# sch.net
KiCad netlist of a schematic drawn in Altium Designer
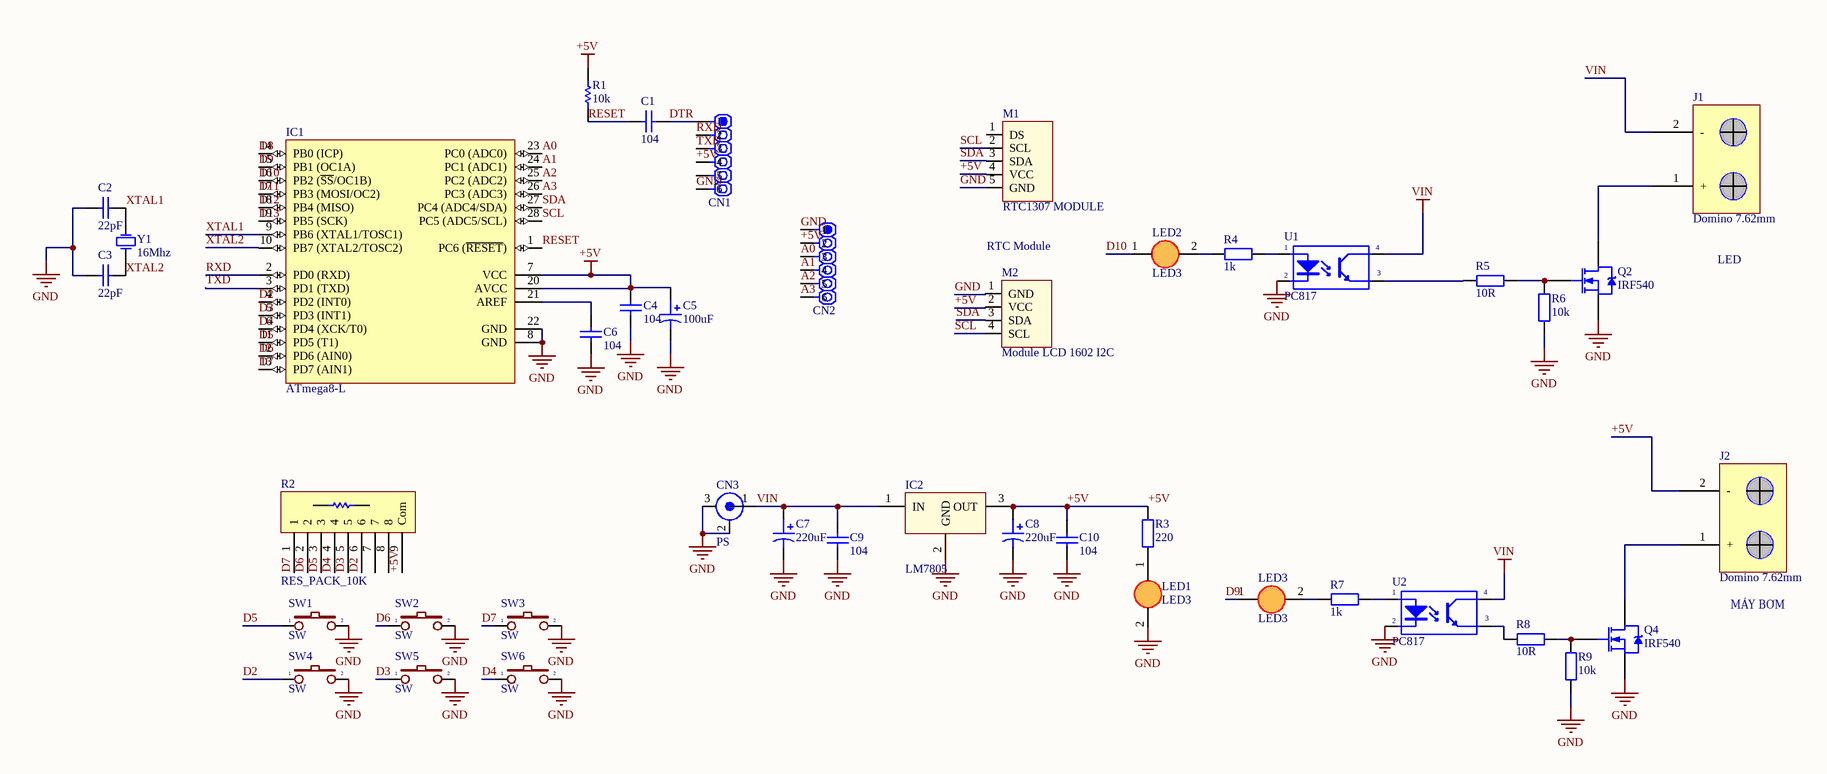
[diagram p0: sch.SchDoc]

(export (version "E")
  (design (tool "Eeschema 10.0.6"))
  (components
    (comp (ref "C1")
      (value "104")
      (footprint "C-NP-0805")
      (description "Non-polarized Capacitor")
      (fields (field (name "Comment") "Cap Non-pol") (field (name "PUBLISHER") "Altium Limited"))
      (libsource (lib "anhlibsch") (part "Cap Non-pol"))
    )
    (comp (ref "C2")
      (value "22pF")
      (footprint "C-NP-0805")
      (description "Non-polarized Capacitor")
      (fields (field (name "Comment") "Cap Non-pol") (field (name "PUBLISHER") "Altium Limited"))
      (libsource (lib "anhlibsch") (part "Cap Non-pol"))
    )
    (comp (ref "C3")
      (value "22pF")
      (footprint "C-NP-0805")
      (description "Non-polarized Capacitor")
      (fields (field (name "Comment") "Cap Non-pol") (field (name "PUBLISHER") "Altium Limited"))
      (libsource (lib "anhlibsch") (part "Cap Non-pol"))
    )
    (comp (ref "C4")
      (value "104")
      (footprint "C-NP-0805")
      (description "Non-polarized Capacitor")
      (fields (field (name "Comment") "Cap Non-pol") (field (name "PUBLISHER") "Altium Limited"))
      (libsource (lib "anhlibsch") (part "Cap Non-pol"))
    )
    (comp (ref "C5")
      (value "100uF")
      (footprint "RADIAL D")
      (description "Polarized Capacitor")
      (fields (field (name "Comment") "Cap Pol") (field (name "PUBLISHER") "Altium Limited"))
      (libsource (lib "anhlibsch") (part "Cap Pol"))
    )
    (comp (ref "C6")
      (value "104")
      (footprint "C-NP-0805")
      (description "Non-polarized Capacitor")
      (fields (field (name "Comment") "Cap Non-pol") (field (name "PUBLISHER") "Altium Limited"))
      (libsource (lib "anhlibsch") (part "Cap Non-pol"))
    )
    (comp (ref "C7")
      (value "220uF")
      (footprint "RADIAL E")
      (description "Polarized Capacitor")
      (fields (field (name "Comment") "Cap Pol") (field (name "PUBLISHER") "Altium Limited"))
      (libsource (lib "anhlibsch") (part "Cap Pol"))
    )
    (comp (ref "C8")
      (value "220uF")
      (footprint "RADIAL E")
      (description "Polarized Capacitor")
      (fields (field (name "Comment") "Cap Pol") (field (name "PUBLISHER") "Altium Limited"))
      (libsource (lib "anhlibsch") (part "Cap Pol"))
    )
    (comp (ref "C9")
      (value "104")
      (footprint "Cap Non-Pol 3mm")
      (description "Non-polarized Capacitor")
      (fields (field (name "Comment") "Cap Non-pol") (field (name "PUBLISHER") "Altium Limited"))
      (libsource (lib "anhlibsch") (part "Cap Non-pol"))
    )
    (comp (ref "C10")
      (value "104")
      (footprint "Cap Non-Pol 3mm")
      (description "Non-polarized Capacitor")
      (fields (field (name "Comment") "Cap Non-pol") (field (name "PUBLISHER") "Altium Limited"))
      (libsource (lib "anhlibsch") (part "Cap Non-pol"))
    )
    (comp (ref "CN1")
      (value "IO")
      (footprint "CON.HDR1X6")
      (description "Header 1x6")
      (fields (field (name "PUBLISHER") "Hoang Nguyen"))
      (libsource (lib "anhlibsch") (part "CON.HDR1x6"))
    )
    (comp (ref "CN2")
      (value "IO")
      (footprint "CON.HDR1X6")
      (description "Header 1x6")
      (fields (field (name "PUBLISHER") "Hoang Nguyen"))
      (libsource (lib "anhlibsch") (part "CON.HDR1x6"))
    )
    (comp (ref "CN3")
      (value "PS")
      (footprint "JACK DC")
      (description "DC Power Jack, 2.5mm, KLD Series, PCB Mount")
      (libsource (lib "anhlibsch") (part "CON.DCjack"))
    )
    (comp (ref "IC1")
      (value "ATmega8-L")
      (footprint "DIP28/W0.3")
      (description "8-Bit AVR Microcontroller with 8K Bytes of In-System Programmable Flash Memory")
      (libsource (lib "anhlibsch") (part "ATmega8-L"))
    )
    (comp (ref "IC2")
      (value "LM7805")
      (footprint "QTO-220")
      (description "On ap +, from + 5 to + 24VDC")
      (libsource (lib "anhlibsch") (part "LM78xx_1"))
    )
    (comp (ref "J1")
      (value "Domino 7.62mm")
      (footprint "KF7.62")
      (libsource (lib "anhlibsch") (part "Con2-7.62mm"))
    )
    (comp (ref "J2")
      (value "Domino 7.62mm")
      (footprint "KF7.62")
      (libsource (lib "anhlibsch") (part "Con2-7.62mm"))
    )
    (comp (ref "LED1")
      (value "LED3")
      (footprint "LED3mm")
      (description "LED 3mm")
      (libsource (lib "anhlibsch") (part "LED 3mm"))
    )
    (comp (ref "LED2")
      (value "LED3")
      (footprint "LED3mm")
      (description "LED 3mm")
      (libsource (lib "anhlibsch") (part "LED 3mm"))
    )
    (comp (ref "LED3")
      (value "LED3")
      (footprint "LED3mm")
      (description "LED 3mm")
      (libsource (lib "anhlibsch") (part "LED 3mm"))
    )
    (comp (ref "M1")
      (value "RTC1307 MODULE")
      (footprint "RTCmODULE")
      (libsource (lib "anhlibsch") (part "RTC1307_MODULE"))
    )
    (comp (ref "M2")
      (value "Module LCD 1602 I2C")
      (footprint "LCD1602_I2C")
      (libsource (lib "anhlibsch") (part "LCD1602_I2C"))
    )
    (comp (ref "Q2")
      (value "IRF540")
      (footprint "TO-220-3")
      (description "HEXFET N-Channel Power MOSFET")
      (fields (field (name "PUBLISHER") "Altium Limited"))
      (libsource (lib "anhlibsch") (part "IRF540"))
    )
    (comp (ref "Q4")
      (value "IRF540")
      (footprint "TO-220-3")
      (description "HEXFET N-Channel Power MOSFET")
      (fields (field (name "PUBLISHER") "Altium Limited"))
      (libsource (lib "anhlibsch") (part "IRF540"))
    )
    (comp (ref "R1")
      (value "10k")
      (footprint "R-0805")
      (description "Resistor")
      (fields (field (name "Comment") "RESISTOR") (field (name "PUBLISHER") "Altium Limited"))
      (libsource (lib "anhlibsch") (part "RESISTOR"))
    )
    (comp (ref "R2")
      (value "RES_PACK_10K")
      (footprint "Res Array")
      (description "Isolated Resistor Network")
      (fields (field (name "PUBLISHER") "Altium Limited"))
      (libsource (lib "anhlibsch") (part "RES_PACK_8R"))
    )
    (comp (ref "R3")
      (value "220")
      (footprint "R1/4W")
      (description "Resistor 1/4W")
      (libsource (lib "anhlibsch") (part "R1/4W"))
    )
    (comp (ref "R4")
      (value "1k")
      (footprint "R1/4W")
      (description "Resistor 1/4W")
      (libsource (lib "anhlibsch") (part "R1/4W"))
    )
    (comp (ref "R5")
      (value "10R")
      (footprint "R1/4W")
      (description "Resistor 1/4W")
      (libsource (lib "anhlibsch") (part "R1/4W"))
    )
    (comp (ref "R6")
      (value "10k")
      (footprint "R1/4W")
      (description "Resistor 1/4W")
      (libsource (lib "anhlibsch") (part "R1/4W"))
    )
    (comp (ref "R7")
      (value "1k")
      (footprint "R1/4W")
      (description "Resistor 1/4W")
      (libsource (lib "anhlibsch") (part "R1/4W"))
    )
    (comp (ref "R8")
      (value "10R")
      (footprint "R1/4W")
      (description "Resistor 1/4W")
      (libsource (lib "anhlibsch") (part "R1/4W"))
    )
    (comp (ref "R9")
      (value "10k")
      (footprint "R1/4W")
      (description "Resistor 1/4W")
      (libsource (lib "anhlibsch") (part "R1/4W"))
    )
    (comp (ref "SW1")
      (value "SW")
      (footprint "SW2")
      (description "Switch button 2 pin")
      (libsource (lib "anhlibsch") (part "SW2"))
    )
    (comp (ref "SW2")
      (value "SW")
      (footprint "SW2")
      (description "Switch button 2 pin")
      (libsource (lib "anhlibsch") (part "SW2"))
    )
    (comp (ref "SW3")
      (value "SW")
      (footprint "SW2")
      (description "Switch button 2 pin")
      (libsource (lib "anhlibsch") (part "SW2"))
    )
    (comp (ref "SW4")
      (value "SW")
      (footprint "SW2")
      (description "Switch button 2 pin")
      (libsource (lib "anhlibsch") (part "SW2"))
    )
    (comp (ref "SW5")
      (value "SW")
      (footprint "SW2")
      (description "Switch button 2 pin")
      (libsource (lib "anhlibsch") (part "SW2"))
    )
    (comp (ref "SW6")
      (value "SW")
      (footprint "SW2")
      (description "Switch button 2 pin")
      (libsource (lib "anhlibsch") (part "SW2"))
    )
    (comp (ref "U1")
      (value "PC817")
      (footprint "DIP4/W0.3")
      (description "Single Opto")
      (libsource (lib "anhlibsch") (part "PC817_1"))
    )
    (comp (ref "U2")
      (value "PC817")
      (footprint "DIP4/W0.3")
      (description "Single Opto")
      (libsource (lib "anhlibsch") (part "PC817_1"))
    )
    (comp (ref "Y1")
      (value "16Mhz")
      (footprint "XTAL")
      (description "Crystal Oscillator")
      (fields (field (name "PUBLISHER") "Altium Limited"))
      (libsource (lib "anhlibsch") (part "XTAL"))
    )
  )
  (nets
    (net (code "1") (name "+5V") (class "Default")
      (node (ref "C10") (pin "1") (pinfunction "1_1") (pintype "passive"))
      (node (ref "C4") (pin "2") (pinfunction "2_2") (pintype "passive"))
      (node (ref "C5") (pin "1") (pinfunction "1_1") (pintype "passive"))
      (node (ref "C8") (pin "1") (pinfunction "1_1") (pintype "passive"))
      (node (ref "CN1") (pin "4") (pinfunction "4_4") (pintype "passive"))
      (node (ref "CN2") (pin "2") (pinfunction "2_2") (pintype "passive"))
      (node (ref "IC1") (pin "20") (pinfunction "AVCC_20") (pintype "power_in"))
      (node (ref "IC1") (pin "7") (pinfunction "VCC_7") (pintype "power_in"))
      (node (ref "IC2") (pin "3") (pinfunction "OUT_3") (pintype "passive"))
      (node (ref "J2") (pin "2") (pinfunction "-_2") (pintype "passive"))
      (node (ref "M1") (pin "4") (pinfunction "VCC_4") (pintype "passive"))
      (node (ref "M2") (pin "2") (pinfunction "VCC_2") (pintype "passive"))
      (node (ref "R1") (pin "2") (pinfunction "2_2") (pintype "passive"))
      (node (ref "R2") (pin "9") (pinfunction "Com_9") (pintype "passive"))
      (node (ref "R3") (pin "2") (pinfunction "2_2") (pintype "passive"))
    )
    (net (code "2") (name "/A0") (class "Default")
      (node (ref "CN2") (pin "3") (pinfunction "3_3") (pintype "passive"))
      (node (ref "IC1") (pin "23") (pinfunction "PC0_(ADC0)_23") (pintype "bidirectional"))
    )
    (net (code "3") (name "/A1") (class "Default")
      (node (ref "CN2") (pin "4") (pinfunction "4_4") (pintype "passive"))
      (node (ref "IC1") (pin "24") (pinfunction "PC1_(ADC1)_24") (pintype "bidirectional"))
    )
    (net (code "4") (name "/A2") (class "Default")
      (node (ref "CN2") (pin "5") (pinfunction "5_5") (pintype "passive"))
      (node (ref "IC1") (pin "25") (pinfunction "PC2_(ADC2)_25") (pintype "bidirectional"))
    )
    (net (code "5") (name "/A3") (class "Default")
      (node (ref "CN2") (pin "6") (pinfunction "6_6") (pintype "passive"))
      (node (ref "IC1") (pin "26") (pinfunction "PC3_(ADC3)_26") (pintype "bidirectional"))
    )
    (net (code "6") (name "/D2") (class "Default")
      (node (ref "IC1") (pin "4") (pinfunction "PD2_(INT0)_4") (pintype "bidirectional"))
      (node (ref "R2") (pin "6") (pinfunction "6_6") (pintype "passive"))
      (node (ref "SW4") (pin "1") (pinfunction "1_1") (pintype "passive"))
    )
    (net (code "7") (name "/D3") (class "Default")
      (node (ref "IC1") (pin "5") (pinfunction "PD3_(INT1)_5") (pintype "bidirectional"))
      (node (ref "R2") (pin "5") (pinfunction "5_5") (pintype "passive"))
      (node (ref "SW5") (pin "1") (pinfunction "1_1") (pintype "passive"))
    )
    (net (code "8") (name "/D4") (class "Default")
      (node (ref "IC1") (pin "6") (pinfunction "PD4_(XCK/T0)_6") (pintype "bidirectional"))
      (node (ref "R2") (pin "4") (pinfunction "4_4") (pintype "passive"))
      (node (ref "SW6") (pin "1") (pinfunction "1_1") (pintype "passive"))
    )
    (net (code "9") (name "/D5") (class "Default")
      (node (ref "IC1") (pin "11") (pinfunction "PD5_(T1)_11") (pintype "bidirectional"))
      (node (ref "R2") (pin "3") (pinfunction "3_3") (pintype "passive"))
      (node (ref "SW1") (pin "1") (pinfunction "1_1") (pintype "passive"))
    )
    (net (code "10") (name "/D6") (class "Default")
      (node (ref "IC1") (pin "12") (pinfunction "PD6_(AIN0)_12") (pintype "bidirectional"))
      (node (ref "R2") (pin "2") (pinfunction "2_2") (pintype "passive"))
      (node (ref "SW2") (pin "1") (pinfunction "1_1") (pintype "passive"))
    )
    (net (code "11") (name "/D7") (class "Default")
      (node (ref "IC1") (pin "13") (pinfunction "PD7_(AIN1)_13") (pintype "bidirectional"))
      (node (ref "R2") (pin "1") (pinfunction "1_1") (pintype "passive"))
      (node (ref "SW3") (pin "1") (pinfunction "1_1") (pintype "passive"))
    )
    (net (code "12") (name "/D8") (class "Default")
      (node (ref "IC1") (pin "14") (pinfunction "PB0_(ICP)_14") (pintype "bidirectional"))
    )
    (net (code "13") (name "/D9") (class "Default")
      (node (ref "IC1") (pin "15") (pinfunction "PB1_(OC1A)_15") (pintype "bidirectional"))
      (node (ref "LED3") (pin "1") (pinfunction "A_1") (pintype "passive"))
    )
    (net (code "14") (name "/D10") (class "Default")
      (node (ref "IC1") (pin "16") (pinfunction "PB2_(~{SS}/OC1B)_16") (pintype "bidirectional"))
      (node (ref "LED2") (pin "1") (pinfunction "A_1") (pintype "passive"))
    )
    (net (code "15") (name "/D11") (class "Default")
      (node (ref "IC1") (pin "17") (pinfunction "PB3_(MOSI/OC2)_17") (pintype "bidirectional"))
    )
    (net (code "16") (name "/D12") (class "Default")
      (node (ref "IC1") (pin "18") (pinfunction "PB4_(MISO)_18") (pintype "bidirectional"))
    )
    (net (code "17") (name "/D13") (class "Default")
      (node (ref "IC1") (pin "19") (pinfunction "PB5_(SCK)_19") (pintype "bidirectional"))
    )
    (net (code "18") (name "/DTR") (class "Default")
      (node (ref "C1") (pin "1") (pinfunction "1_1") (pintype "passive"))
      (node (ref "CN1") (pin "1") (pinfunction "1_1") (pintype "passive"))
    )
    (net (code "19") (name "/RESET") (class "Default")
      (node (ref "C1") (pin "2") (pinfunction "2_2") (pintype "passive"))
      (node (ref "IC1") (pin "1") (pinfunction "PC6_(~{RESET})_1") (pintype "bidirectional"))
      (node (ref "R1") (pin "1") (pinfunction "1_1") (pintype "passive"))
    )
    (net (code "20") (name "/RXD") (class "Default")
      (node (ref "CN1") (pin "2") (pinfunction "2_2") (pintype "passive"))
      (node (ref "IC1") (pin "2") (pinfunction "PD0_(RXD)_2") (pintype "bidirectional"))
    )
    (net (code "21") (name "/SCL") (class "Default")
      (node (ref "IC1") (pin "28") (pinfunction "PC5_(ADC5/SCL)_28") (pintype "bidirectional"))
      (node (ref "M1") (pin "2") (pinfunction "SCL_2") (pintype "passive"))
      (node (ref "M2") (pin "4") (pinfunction "SCL_4") (pintype "passive"))
    )
    (net (code "22") (name "/SDA") (class "Default")
      (node (ref "IC1") (pin "27") (pinfunction "PC4_(ADC4/SDA)_27") (pintype "bidirectional"))
      (node (ref "M1") (pin "3") (pinfunction "SDA_3") (pintype "passive"))
      (node (ref "M2") (pin "3") (pinfunction "SDA_3") (pintype "passive"))
    )
    (net (code "23") (name "/TXD") (class "Default")
      (node (ref "CN1") (pin "3") (pinfunction "3_3") (pintype "passive"))
      (node (ref "IC1") (pin "3") (pinfunction "PD1_(TXD)_3") (pintype "bidirectional"))
    )
    (net (code "24") (name "/XTAL1") (class "Default")
      (node (ref "C2") (pin "2") (pinfunction "2_2") (pintype "passive"))
      (node (ref "IC1") (pin "9") (pinfunction "PB6_(XTAL1/TOSC1)_9") (pintype "bidirectional"))
      (node (ref "Y1") (pin "2") (pinfunction "OSC2_2") (pintype "passive"))
    )
    (net (code "25") (name "/XTAL2") (class "Default")
      (node (ref "C3") (pin "2") (pinfunction "2_2") (pintype "passive"))
      (node (ref "IC1") (pin "10") (pinfunction "PB7_(XTAL2/TOSC2)_10") (pintype "bidirectional"))
      (node (ref "Y1") (pin "1") (pinfunction "OSC1_1") (pintype "passive"))
    )
    (net (code "26") (name "GND") (class "Default")
      (node (ref "C10") (pin "2") (pinfunction "2_2") (pintype "passive"))
      (node (ref "C2") (pin "1") (pinfunction "1_1") (pintype "passive"))
      (node (ref "C3") (pin "1") (pinfunction "1_1") (pintype "passive"))
      (node (ref "C4") (pin "1") (pinfunction "1_1") (pintype "passive"))
      (node (ref "C5") (pin "2") (pinfunction "2_2") (pintype "passive"))
      (node (ref "C6") (pin "1") (pinfunction "1_1") (pintype "passive"))
      (node (ref "C7") (pin "2") (pinfunction "2_2") (pintype "passive"))
      (node (ref "C8") (pin "2") (pinfunction "2_2") (pintype "passive"))
      (node (ref "C9") (pin "2") (pinfunction "2_2") (pintype "passive"))
      (node (ref "CN1") (pin "6") (pinfunction "6_6") (pintype "passive"))
      (node (ref "CN2") (pin "1") (pinfunction "1_1") (pintype "passive"))
      (node (ref "CN3") (pin "2") (pinfunction "SHIELD_2") (pintype "power_in"))
      (node (ref "CN3") (pin "3") (pinfunction "SHIELD_3") (pintype "passive"))
      (node (ref "IC1") (pin "22") (pinfunction "GND_22") (pintype "power_in"))
      (node (ref "IC1") (pin "8") (pinfunction "GND_8") (pintype "power_in"))
      (node (ref "IC2") (pin "2") (pinfunction "GND_2") (pintype "passive"))
      (node (ref "LED1") (pin "2") (pinfunction "K_2") (pintype "passive"))
      (node (ref "M1") (pin "5") (pinfunction "GND_5") (pintype "passive"))
      (node (ref "M2") (pin "1") (pinfunction "GND_1") (pintype "passive"))
      (node (ref "Q2") (pin "3") (pinfunction "S_3") (pintype "passive"))
      (node (ref "Q4") (pin "3") (pinfunction "S_3") (pintype "passive"))
      (node (ref "R6") (pin "1") (pinfunction "1_1") (pintype "passive"))
      (node (ref "R9") (pin "1") (pinfunction "1_1") (pintype "passive"))
      (node (ref "SW1") (pin "2") (pinfunction "2_2") (pintype "passive"))
      (node (ref "SW2") (pin "2") (pinfunction "2_2") (pintype "passive"))
      (node (ref "SW3") (pin "2") (pinfunction "2_2") (pintype "passive"))
      (node (ref "SW4") (pin "2") (pinfunction "2_2") (pintype "passive"))
      (node (ref "SW5") (pin "2") (pinfunction "2_2") (pintype "passive"))
      (node (ref "SW6") (pin "2") (pinfunction "2_2") (pintype "passive"))
      (node (ref "U1") (pin "2") (pinfunction "K_2") (pintype "passive"))
      (node (ref "U2") (pin "2") (pinfunction "K_2") (pintype "passive"))
    )
    (net (code "27") (name "Net-(IC1-AREF)") (class "Default")
      (node (ref "C6") (pin "2") (pinfunction "2_2") (pintype "passive"))
      (node (ref "IC1") (pin "21") (pinfunction "AREF_21") (pintype "passive"))
    )
    (net (code "28") (name "Net-(J1-+)") (class "Default")
      (node (ref "J1") (pin "1") (pinfunction "+_1") (pintype "passive"))
      (node (ref "Q2") (pin "2") (pinfunction "D_2") (pintype "passive"))
    )
    (net (code "29") (name "Net-(J2-+)") (class "Default")
      (node (ref "J2") (pin "1") (pinfunction "+_1") (pintype "passive"))
      (node (ref "Q4") (pin "2") (pinfunction "D_2") (pintype "passive"))
    )
    (net (code "30") (name "Net-(LED1-A)") (class "Default")
      (node (ref "LED1") (pin "1") (pinfunction "A_1") (pintype "passive"))
      (node (ref "R3") (pin "1") (pinfunction "1_1") (pintype "passive"))
    )
    (net (code "31") (name "Net-(LED2-K)") (class "Default")
      (node (ref "LED2") (pin "2") (pinfunction "K_2") (pintype "passive"))
      (node (ref "R4") (pin "2") (pinfunction "2_2") (pintype "passive"))
    )
    (net (code "32") (name "Net-(LED3-K)") (class "Default")
      (node (ref "LED3") (pin "2") (pinfunction "K_2") (pintype "passive"))
      (node (ref "R7") (pin "2") (pinfunction "2_2") (pintype "passive"))
    )
    (net (code "33") (name "Net-(Q2-G)") (class "Default")
      (node (ref "Q2") (pin "1") (pinfunction "G_1") (pintype "passive"))
      (node (ref "R5") (pin "2") (pinfunction "2_2") (pintype "passive"))
      (node (ref "R6") (pin "2") (pinfunction "2_2") (pintype "passive"))
    )
    (net (code "34") (name "Net-(Q4-G)") (class "Default")
      (node (ref "Q4") (pin "1") (pinfunction "G_1") (pintype "passive"))
      (node (ref "R8") (pin "2") (pinfunction "2_2") (pintype "passive"))
      (node (ref "R9") (pin "2") (pinfunction "2_2") (pintype "passive"))
    )
    (net (code "35") (name "Net-(U1-A)") (class "Default")
      (node (ref "R4") (pin "1") (pinfunction "1_1") (pintype "passive"))
      (node (ref "U1") (pin "1") (pinfunction "A_1") (pintype "passive"))
    )
    (net (code "36") (name "Net-(U1-E)") (class "Default")
      (node (ref "R5") (pin "1") (pinfunction "1_1") (pintype "passive"))
      (node (ref "U1") (pin "3") (pinfunction "E_3") (pintype "passive"))
    )
    (net (code "37") (name "Net-(U2-A)") (class "Default")
      (node (ref "R7") (pin "1") (pinfunction "1_1") (pintype "passive"))
      (node (ref "U2") (pin "1") (pinfunction "A_1") (pintype "passive"))
    )
    (net (code "38") (name "Net-(U2-E)") (class "Default")
      (node (ref "R8") (pin "1") (pinfunction "1_1") (pintype "passive"))
      (node (ref "U2") (pin "3") (pinfunction "E_3") (pintype "passive"))
    )
    (net (code "39") (name "VIN") (class "Default")
      (node (ref "C7") (pin "1") (pinfunction "1_1") (pintype "passive"))
      (node (ref "C9") (pin "1") (pinfunction "1_1") (pintype "passive"))
      (node (ref "CN3") (pin "1") (pinfunction "CENTER_1") (pintype "power_in"))
      (node (ref "IC2") (pin "1") (pinfunction "IN_1") (pintype "passive"))
      (node (ref "J1") (pin "2") (pinfunction "-_2") (pintype "passive"))
      (node (ref "U1") (pin "4") (pinfunction "C_4") (pintype "passive"))
      (node (ref "U2") (pin "4") (pinfunction "C_4") (pintype "passive"))
    )
    (net (code "40") (name "unconnected-(CN1-Pad5)") (class "Default")
      (node (ref "CN1") (pin "5") (pinfunction "5_5") (pintype "passive"))
    )
    (net (code "41") (name "unconnected-(M1-DS-Pad1)") (class "Default")
      (node (ref "M1") (pin "1") (pinfunction "DS_1") (pintype "passive"))
    )
    (net (code "42") (name "unconnected-(R2-Pad7)") (class "Default")
      (node (ref "R2") (pin "7") (pinfunction "7_7") (pintype "passive"))
    )
    (net (code "43") (name "unconnected-(R2-Pad8)") (class "Default")
      (node (ref "R2") (pin "8") (pinfunction "8_8") (pintype "passive"))
    )
  )
)
